# Engine_Tachometer.net
KiCad netlist of a schematic drawn in EAGLE
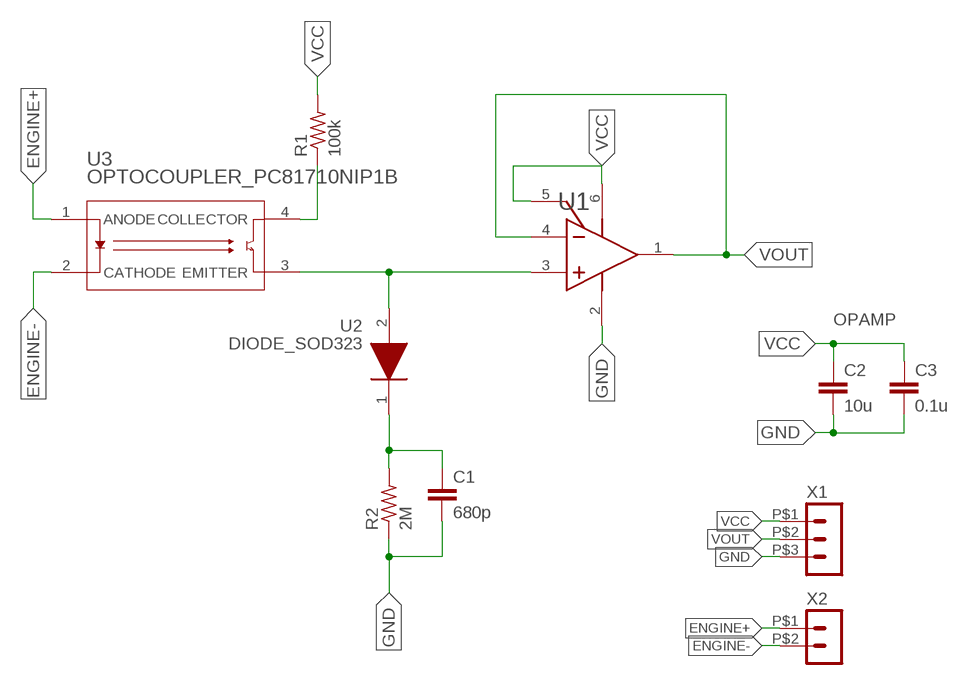
[diagram p0: schematic, sheet 1]

(export (version "E")
  (design (tool "Eeschema 10.0.6"))
  (components
    (comp (ref "C1")
      (value "680p")
      (footprint "eagle-import:C0603")
      (libsource (lib "eagle-import") (part "CAP_SMDC0603"))
    )
    (comp (ref "C2")
      (value "10u")
      (footprint "eagle-import:C1206")
      (libsource (lib "eagle-import") (part "CAP_SMDC1206"))
    )
    (comp (ref "C3")
      (value "0.1u")
      (footprint "eagle-import:C0603")
      (libsource (lib "eagle-import") (part "CAP_SMDC0603"))
    )
    (comp (ref "R1")
      (value "100k")
      (footprint "eagle-import:R1206")
      (libsource (lib "eagle-import") (part "RES_SMDR1206"))
    )
    (comp (ref "R2")
      (value "2M")
      (footprint "eagle-import:R0603")
      (libsource (lib "eagle-import") (part "RES_SMDR0603"))
    )
    (comp (ref "U1")
      (value "OPAMP_LMH6611MKE")
      (footprint "eagle-import:MK06A")
      (fields
        (field (name "MANUFACTURER_PART_NUMBER") "LMH6611MKE/NOPB")
        (field (name "COPYRIGHT") "Copyright (C) 2022 Ultra Librarian. All rights reserved.")
      )
      (libsource (lib "eagle-import") (part "OPAMP_LMH6611MKE"))
    )
    (comp (ref "U2")
      (value "DIODE_SOD323")
      (footprint "eagle-import:SOD-323_1P8X1P35_ONS")
      (fields
        (field (name "MANUFACTURER_PART_NUMBER") "MM3Z33VT1G")
        (field (name "COPYRIGHT") "Copyright (C) 2022 Ultra Librarian. All rights reserved.")
      )
      (libsource (lib "eagle-import") (part "DIODE_SOD323"))
    )
    (comp (ref "U3")
      (value "OPTOCOUPLER_PC81710NIP1B")
      (footprint "eagle-import:SOP_PC8171_SCT")
      (fields
        (field (name "MANUFACTURER_PART_NUMBER") "PC81710NIP1B")
        (field (name "COPYRIGHT") "Copyright (C) 2022 Ultra Librarian. All rights reserved.")
      )
      (libsource (lib "eagle-import") (part "OPTOCOUPLER_PC81710NIP1B"))
    )
    (comp (ref "X1")
      (value "HEADER_POS3_43650-0300")
      (footprint "eagle-import:43650-0300")
      (libsource (lib "eagle-import") (part "HEADER_POS3_?43650-0300"))
    )
    (comp (ref "X2")
      (value "HEADER_POS2_43650-0200")
      (footprint "eagle-import:43650-0200")
      (libsource (lib "eagle-import") (part "HEADER_POS2_?43650-0200"))
    )
  )
  (nets
    (net (code "1") (name "ENGINE+") (class "Default")
      (node (ref "U3") (pin "1") (pinfunction "ANODE_1") (pintype "passive"))
      (node (ref "X2") (pin "P$1") (pinfunction "1_P$1") (pintype "passive"))
    )
    (net (code "2") (name "ENGINE-") (class "Default")
      (node (ref "U3") (pin "2") (pinfunction "CATHODE_2") (pintype "passive"))
      (node (ref "X2") (pin "P$2") (pinfunction "2_P$2") (pintype "passive"))
    )
    (net (code "3") (name "GND") (class "Default")
      (node (ref "C1") (pin "2") (pinfunction "2_2") (pintype "passive"))
      (node (ref "C2") (pin "2") (pinfunction "2_2") (pintype "passive"))
      (node (ref "C3") (pin "2") (pinfunction "2_2") (pintype "passive"))
      (node (ref "R2") (pin "1") (pinfunction "1_1") (pintype "passive"))
      (node (ref "U1") (pin "2") (pinfunction "V-_2") (pintype "power_in"))
      (node (ref "X1") (pin "P$3") (pinfunction "3_P$3") (pintype "passive"))
    )
    (net (code "4") (name "Net-(C1-Pad1)") (class "Default")
      (node (ref "C1") (pin "1") (pinfunction "1_1") (pintype "passive"))
      (node (ref "R2") (pin "2") (pinfunction "2_2") (pintype "passive"))
      (node (ref "U2") (pin "1") (pinfunction "1_1") (pintype "bidirectional"))
    )
    (net (code "5") (name "Net-(U1-IN+)") (class "Default")
      (node (ref "U1") (pin "3") (pinfunction "IN+_3") (pintype "input"))
      (node (ref "U2") (pin "2") (pinfunction "2_2") (pintype "bidirectional"))
      (node (ref "U3") (pin "3") (pinfunction "EMITTER_3") (pintype "passive"))
    )
    (net (code "6") (name "Net-(U3-COLLECTOR)") (class "Default")
      (node (ref "R1") (pin "1") (pinfunction "1_1") (pintype "passive"))
      (node (ref "U3") (pin "4") (pinfunction "COLLECTOR_4") (pintype "passive"))
    )
    (net (code "7") (name "VCC") (class "Default")
      (node (ref "C2") (pin "1") (pinfunction "1_1") (pintype "passive"))
      (node (ref "C3") (pin "1") (pinfunction "1_1") (pintype "passive"))
      (node (ref "R1") (pin "2") (pinfunction "2_2") (pintype "passive"))
      (node (ref "U1") (pin "5") (pinfunction "~{DIS}_5") (pintype "passive"))
      (node (ref "U1") (pin "6") (pinfunction "V+_6") (pintype "power_in"))
      (node (ref "X1") (pin "P$1") (pinfunction "1_P$1") (pintype "passive"))
    )
    (net (code "8") (name "VOUT") (class "Default")
      (node (ref "U1") (pin "1") (pinfunction "OUT_1") (pintype "output"))
      (node (ref "U1") (pin "4") (pinfunction "IN-_4") (pintype "input"))
      (node (ref "X1") (pin "P$2") (pinfunction "2_P$2") (pintype "passive"))
    )
  )
)
